# untitled.net
KiCad netlist of a schematic drawn in EAGLE
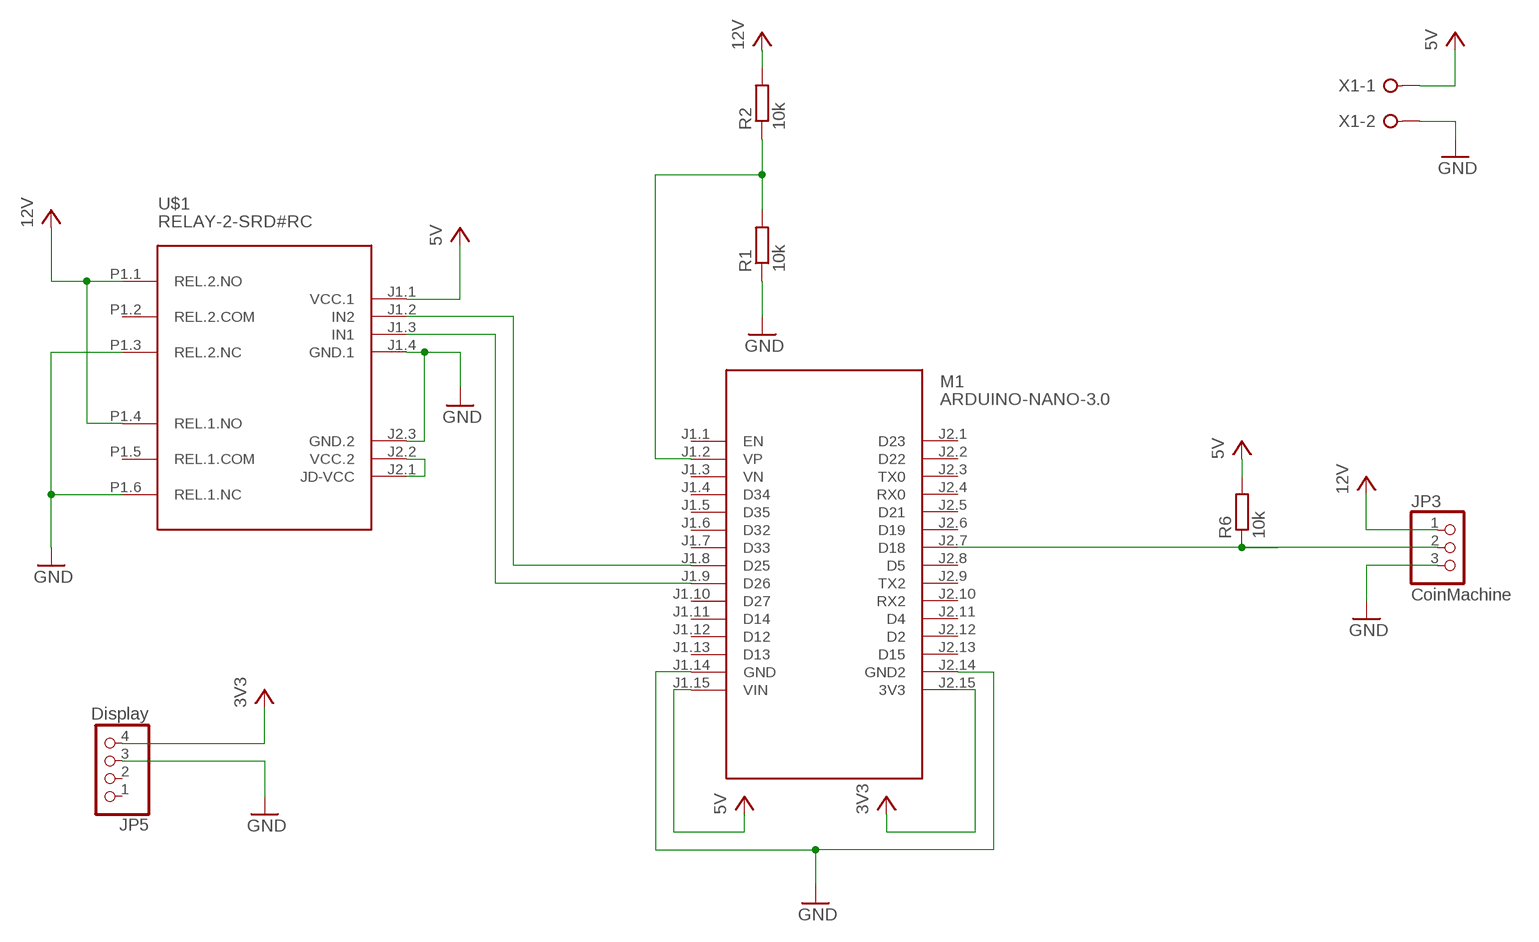
[diagram p0: schematic, sheet 1]

(export (version "E")
  (design (tool "Eeschema 10.0.6"))
  (components
    (comp (ref "JP3")
      (value "CoinMachine")
      (footprint "eagle-import:1X03_90")
      (libsource (lib "eagle-import") (part "PINHD-1X3/90"))
    )
    (comp (ref "JP5")
      (value "Display")
      (footprint "eagle-import:1X04")
      (libsource (lib "eagle-import") (part "PINHD-1X4"))
    )
    (comp (ref "M1")
      (value "ARDUINO-NANO-3.0")
      (footprint "eagle-import:ARDUINO-NANO-3.0")
      (libsource (lib "eagle-import") (part "ARDUINO-NANO-3.0"))
    )
    (comp (ref "R1")
      (value "10k")
      (footprint "eagle-import:0207_10")
      (libsource (lib "eagle-import") (part "R-EU_0207/10"))
    )
    (comp (ref "R2")
      (value "10k")
      (footprint "eagle-import:0207_10")
      (libsource (lib "eagle-import") (part "R-EU_0207/10"))
    )
    (comp (ref "R6")
      (value "10k")
      (footprint "eagle-import:0207_10")
      (libsource (lib "eagle-import") (part "R-EU_0207/10"))
    )
    (comp (ref "U$1")
      (value "RELAY-2-SRD#RC")
      (footprint "eagle-import:RELAY-2-SRD#RC")
      (libsource (lib "eagle-import") (part "RELAY-2-SRD#RC"))
    )
    (comp (ref "X1")
      (value "W237-02P")
      (footprint "eagle-import:W237-132")
      (libsource (lib "eagle-import") (part "W237-02P"))
    )
  )
  (nets
    (net (code "1") (name "12V") (class "Default")
      (node (ref "JP3") (pin "1") (pinfunction "1_1") (pintype "passive"))
      (node (ref "JP5") (pin "4") (pinfunction "4_4") (pintype "passive"))
      (node (ref "M1") (pin "J1.15") (pinfunction "VIN_J1.15") (pintype "power_in"))
      (node (ref "M1") (pin "J2.15") (pinfunction "3V3_J2.15") (pintype "power_in"))
      (node (ref "R2") (pin "2") (pinfunction "2_2") (pintype "passive"))
      (node (ref "R6") (pin "2") (pinfunction "2_2") (pintype "passive"))
      (node (ref "U$1") (pin "J1.1") (pinfunction "VCC.1_J1.1") (pintype "power_in"))
      (node (ref "U$1") (pin "P1.1") (pinfunction "REL.2.NO_P1.1") (pintype "bidirectional"))
      (node (ref "U$1") (pin "P1.4") (pinfunction "REL.1.NO_P1.4") (pintype "bidirectional"))
      (node (ref "X1") (pin "1") (pinfunction "KL_1") (pintype "passive"))
    )
    (net (code "2") (name "GND") (class "Default")
      (node (ref "JP3") (pin "3") (pinfunction "3_3") (pintype "passive"))
      (node (ref "JP5") (pin "3") (pinfunction "3_3") (pintype "passive"))
      (node (ref "M1") (pin "J1.14") (pinfunction "GND_J1.14") (pintype "power_in"))
      (node (ref "M1") (pin "J2.14") (pinfunction "GND2_J2.14") (pintype "power_in"))
      (node (ref "R1") (pin "1") (pinfunction "1_1") (pintype "passive"))
      (node (ref "U$1") (pin "J1.4") (pinfunction "GND.1_J1.4") (pintype "power_in"))
      (node (ref "U$1") (pin "J2.3") (pinfunction "GND.2_J2.3") (pintype "power_in"))
      (node (ref "U$1") (pin "P1.3") (pinfunction "REL.2.NC_P1.3") (pintype "bidirectional"))
      (node (ref "U$1") (pin "P1.6") (pinfunction "REL.1.NC_P1.6") (pintype "bidirectional"))
      (node (ref "X1") (pin "2") (pinfunction "KL_2") (pintype "passive"))
    )
    (net (code "3") (name "Net-(M1-D18)") (class "Default")
      (node (ref "JP3") (pin "2") (pinfunction "2_2") (pintype "passive"))
      (node (ref "M1") (pin "J2.7") (pinfunction "D18_J2.7") (pintype "bidirectional"))
      (node (ref "R6") (pin "1") (pinfunction "1_1") (pintype "passive"))
    )
    (net (code "4") (name "Net-(M1-D25)") (class "Default")
      (node (ref "M1") (pin "J1.8") (pinfunction "D25_J1.8") (pintype "bidirectional"))
      (node (ref "U$1") (pin "J1.2") (pinfunction "IN2_J1.2") (pintype "bidirectional"))
    )
    (net (code "5") (name "Net-(M1-D26)") (class "Default")
      (node (ref "M1") (pin "J1.9") (pinfunction "D26_J1.9") (pintype "bidirectional"))
      (node (ref "U$1") (pin "J1.3") (pinfunction "IN1_J1.3") (pintype "bidirectional"))
    )
    (net (code "6") (name "Net-(M1-VP)") (class "Default")
      (node (ref "M1") (pin "J1.2") (pinfunction "VP_J1.2") (pintype "bidirectional"))
      (node (ref "R1") (pin "2") (pinfunction "2_2") (pintype "passive"))
      (node (ref "R2") (pin "1") (pinfunction "1_1") (pintype "passive"))
    )
    (net (code "7") (name "Net-(U$1-JD-VCC)") (class "Default")
      (node (ref "U$1") (pin "J2.1") (pinfunction "JD-VCC_J2.1") (pintype "bidirectional"))
      (node (ref "U$1") (pin "J2.2") (pinfunction "VCC.2_J2.2") (pintype "power_in"))
    )
    (net (code "8") (name "unconnected-(JP5-Pad1)") (class "Default")
      (node (ref "JP5") (pin "1") (pinfunction "1_1") (pintype "passive"))
    )
    (net (code "9") (name "unconnected-(JP5-Pad2)") (class "Default")
      (node (ref "JP5") (pin "2") (pinfunction "2_2") (pintype "passive"))
    )
    (net (code "10") (name "unconnected-(M1-D2-PadJ2.12)") (class "Default")
      (node (ref "M1") (pin "J2.12") (pinfunction "D2_J2.12") (pintype "bidirectional"))
    )
    (net (code "11") (name "unconnected-(M1-D4-PadJ2.11)") (class "Default")
      (node (ref "M1") (pin "J2.11") (pinfunction "D4_J2.11") (pintype "bidirectional"))
    )
    (net (code "12") (name "unconnected-(M1-D5-PadJ2.8)") (class "Default")
      (node (ref "M1") (pin "J2.8") (pinfunction "D5_J2.8") (pintype "bidirectional"))
    )
    (net (code "13") (name "unconnected-(M1-D12-PadJ1.12)") (class "Default")
      (node (ref "M1") (pin "J1.12") (pinfunction "D12_J1.12") (pintype "bidirectional"))
    )
    (net (code "14") (name "unconnected-(M1-D13-PadJ1.13)") (class "Default")
      (node (ref "M1") (pin "J1.13") (pinfunction "D13_J1.13") (pintype "bidirectional"))
    )
    (net (code "15") (name "unconnected-(M1-D14-PadJ1.11)") (class "Default")
      (node (ref "M1") (pin "J1.11") (pinfunction "D14_J1.11") (pintype "bidirectional"))
    )
    (net (code "16") (name "unconnected-(M1-D15-PadJ2.13)") (class "Default")
      (node (ref "M1") (pin "J2.13") (pinfunction "D15_J2.13") (pintype "bidirectional"))
    )
    (net (code "17") (name "unconnected-(M1-D19-PadJ2.6)") (class "Default")
      (node (ref "M1") (pin "J2.6") (pinfunction "D19_J2.6") (pintype "bidirectional"))
    )
    (net (code "18") (name "unconnected-(M1-D21-PadJ2.5)") (class "Default")
      (node (ref "M1") (pin "J2.5") (pinfunction "D21_J2.5") (pintype "bidirectional"))
    )
    (net (code "19") (name "unconnected-(M1-D22-PadJ2.2)") (class "Default")
      (node (ref "M1") (pin "J2.2") (pinfunction "D22_J2.2") (pintype "bidirectional"))
    )
    (net (code "20") (name "unconnected-(M1-D23-PadJ2.1)") (class "Default")
      (node (ref "M1") (pin "J2.1") (pinfunction "D23_J2.1") (pintype "bidirectional"))
    )
    (net (code "21") (name "unconnected-(M1-D27-PadJ1.10)") (class "Default")
      (node (ref "M1") (pin "J1.10") (pinfunction "D27_J1.10") (pintype "bidirectional"))
    )
    (net (code "22") (name "unconnected-(M1-D32-PadJ1.6)") (class "Default")
      (node (ref "M1") (pin "J1.6") (pinfunction "D32_J1.6") (pintype "bidirectional"))
    )
    (net (code "23") (name "unconnected-(M1-D33-PadJ1.7)") (class "Default")
      (node (ref "M1") (pin "J1.7") (pinfunction "D33_J1.7") (pintype "bidirectional"))
    )
    (net (code "24") (name "unconnected-(M1-D34-PadJ1.4)") (class "Default")
      (node (ref "M1") (pin "J1.4") (pinfunction "D34_J1.4") (pintype "bidirectional"))
    )
    (net (code "25") (name "unconnected-(M1-D35-PadJ1.5)") (class "Default")
      (node (ref "M1") (pin "J1.5") (pinfunction "D35_J1.5") (pintype "bidirectional"))
    )
    (net (code "26") (name "unconnected-(M1-EN-PadJ1.1)") (class "Default")
      (node (ref "M1") (pin "J1.1") (pinfunction "EN_J1.1") (pintype "bidirectional"))
    )
    (net (code "27") (name "unconnected-(M1-RX0-PadJ2.4)") (class "Default")
      (node (ref "M1") (pin "J2.4") (pinfunction "RX0_J2.4") (pintype "bidirectional"))
    )
    (net (code "28") (name "unconnected-(M1-RX2-PadJ2.10)") (class "Default")
      (node (ref "M1") (pin "J2.10") (pinfunction "RX2_J2.10") (pintype "bidirectional"))
    )
    (net (code "29") (name "unconnected-(M1-TX0-PadJ2.3)") (class "Default")
      (node (ref "M1") (pin "J2.3") (pinfunction "TX0_J2.3") (pintype "bidirectional"))
    )
    (net (code "30") (name "unconnected-(M1-TX2-PadJ2.9)") (class "Default")
      (node (ref "M1") (pin "J2.9") (pinfunction "TX2_J2.9") (pintype "bidirectional"))
    )
    (net (code "31") (name "unconnected-(M1-VN-PadJ1.3)") (class "Default")
      (node (ref "M1") (pin "J1.3") (pinfunction "VN_J1.3") (pintype "bidirectional"))
    )
    (net (code "32") (name "unconnected-(U$1-REL.1.COM-PadP1.5)") (class "Default")
      (node (ref "U$1") (pin "P1.5") (pinfunction "REL.1.COM_P1.5") (pintype "bidirectional"))
    )
    (net (code "33") (name "unconnected-(U$1-REL.2.COM-PadP1.2)") (class "Default")
      (node (ref "U$1") (pin "P1.2") (pinfunction "REL.2.COM_P1.2") (pintype "bidirectional"))
    )
  )
)
